# BLDC_Motor_Controller_ADP3120A.net
KiCad netlist of a schematic drawn in EAGLE
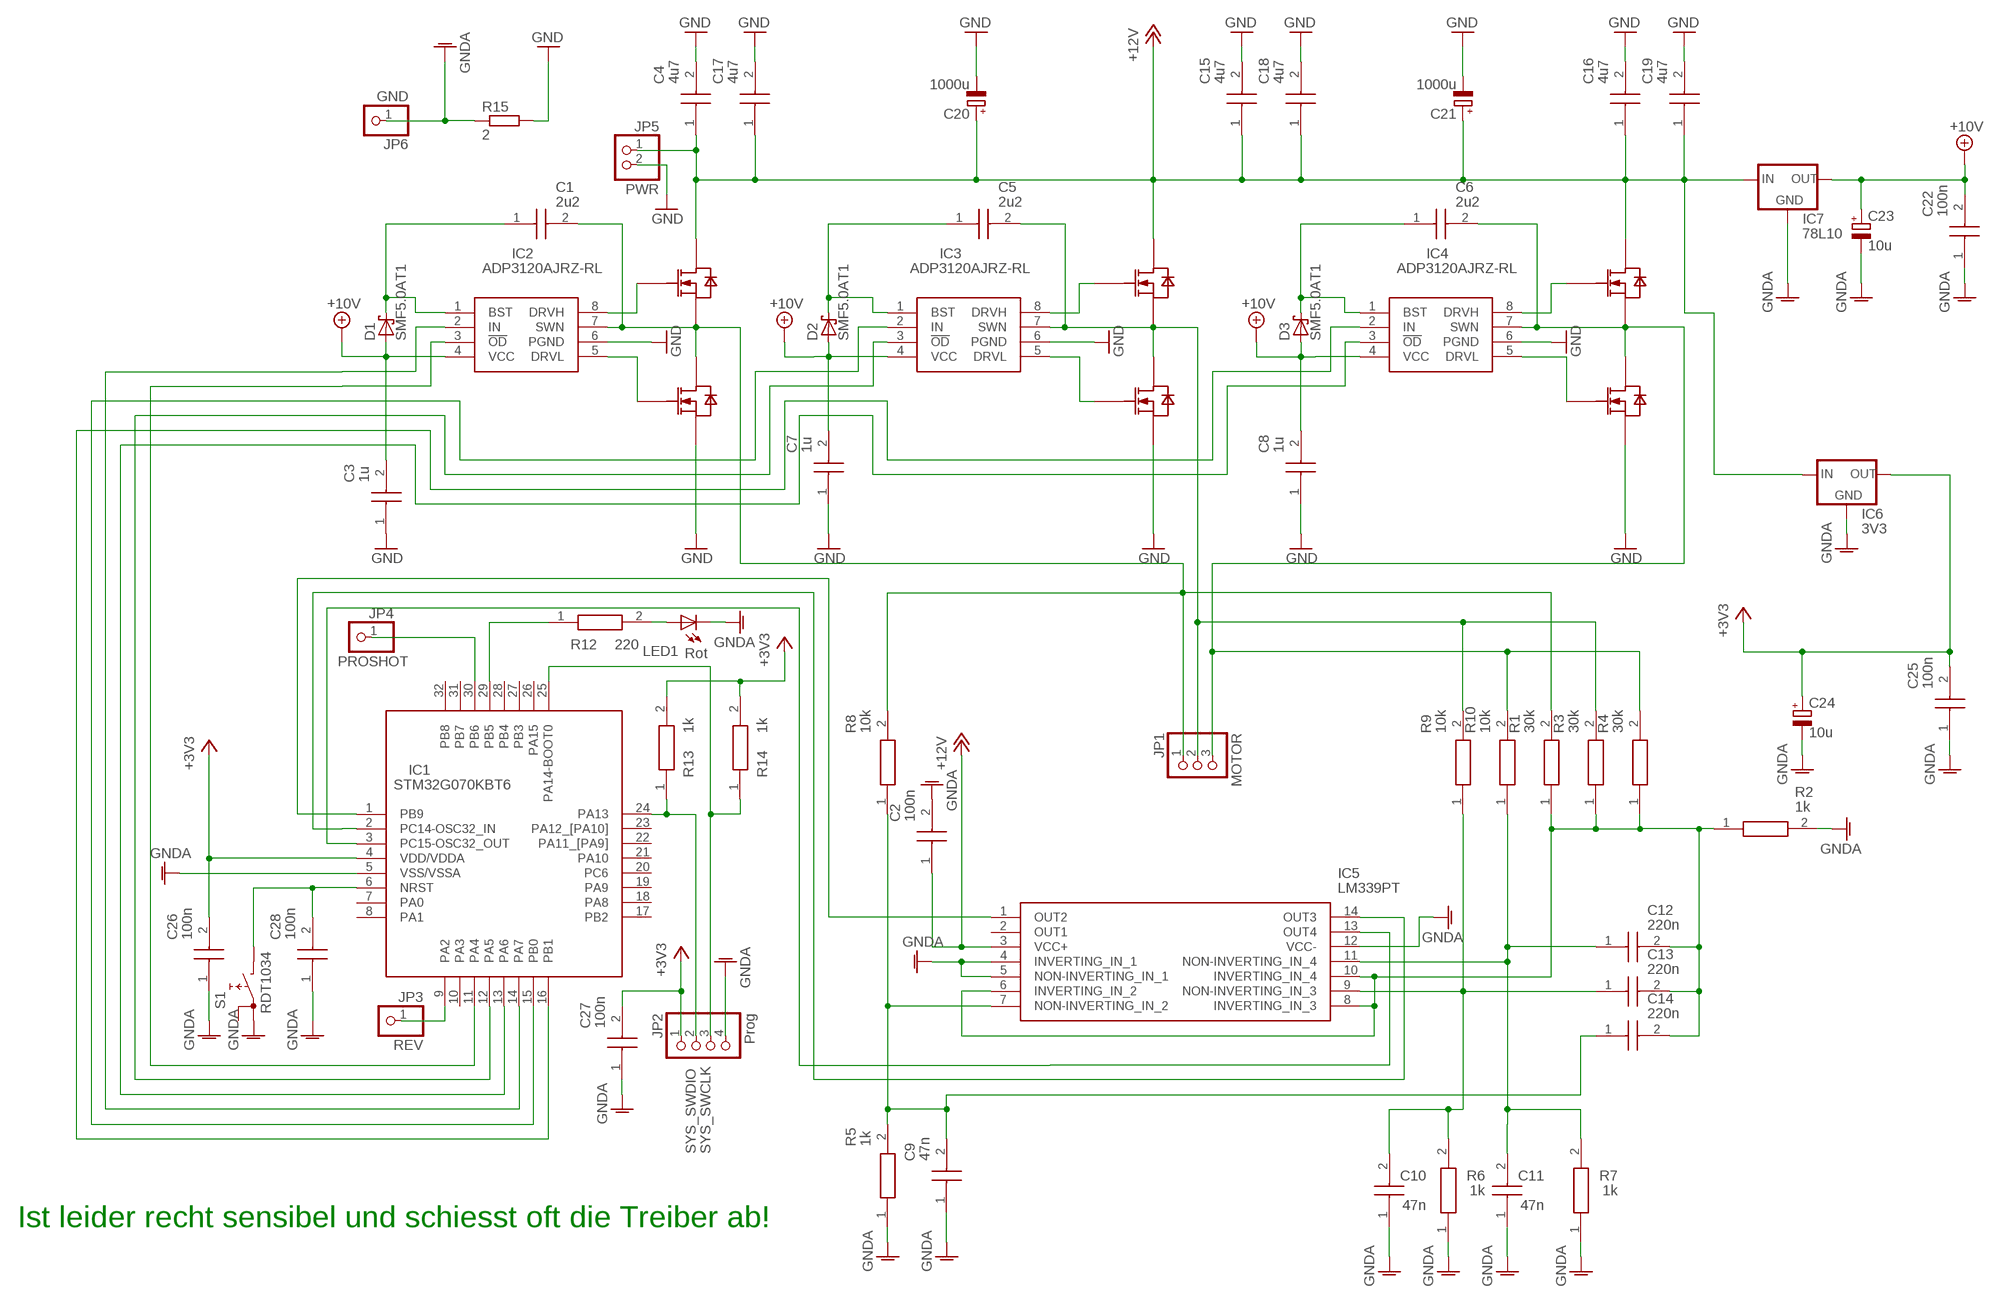
[diagram p0: schematic, sheet 1]

(export (version "E")
  (design (tool "Eeschema 10.0.6"))
  (components
    (comp (ref "C1")
      (value "2u2")
      (footprint "eagle-import:CAPC2012X135N")
      (fields
        (field (name "MANUFACTURER_PART_NUMBER") "CL21B225KAFNNNE")
        (field (name "MOUSER_PART_NUMBER") "187-CL21B225KAFNNNE")
      )
      (libsource (lib "eagle-import") (part "CL21B225KAFNNNE"))
    )
    (comp (ref "C2")
      (value "100n")
      (footprint "eagle-import:CAPC2012X145N")
      (fields
        (field (name "MANUFACTURER_PART_NUMBER") "C2012X7T2E104M125AE")
        (field (name "MOUSER_PART_NUMBER") "810-C2012X7T2E104MST")
      )
      (libsource (lib "eagle-import") (part "C2012X7T2E104M125AE"))
    )
    (comp (ref "C3")
      (value "1u")
      (footprint "eagle-import:GRM31X")
      (fields
        (field (name "MANUFACTURER_PART_NUMBER") "GRM31CC72A475KE11K")
        (field (name "MOUSER_PART_NUMBER") "81-GRM31CC72A475KE1K")
      )
      (libsource (lib "eagle-import") (part "SamacSys_Parts_GRM31CC72A475KE11K"))
    )
    (comp (ref "C4")
      (value "4u7")
      (footprint "eagle-import:GRM31X")
      (fields
        (field (name "MANUFACTURER_PART_NUMBER") "GRM31CC72A475KE11K")
        (field (name "MOUSER_PART_NUMBER") "81-GRM31CC72A475KE1K")
      )
      (libsource (lib "eagle-import") (part "GRM31CC72A475KE11K"))
    )
    (comp (ref "C5")
      (value "2u2")
      (footprint "eagle-import:CAPC2012X135N")
      (fields
        (field (name "MANUFACTURER_PART_NUMBER") "CL21B225KAFNNNE")
        (field (name "MOUSER_PART_NUMBER") "187-CL21B225KAFNNNE")
      )
      (libsource (lib "eagle-import") (part "CL21B225KAFNNNE"))
    )
    (comp (ref "C6")
      (value "2u2")
      (footprint "eagle-import:CAPC2012X135N")
      (fields
        (field (name "MANUFACTURER_PART_NUMBER") "CL21B225KAFNNNE")
        (field (name "MOUSER_PART_NUMBER") "187-CL21B225KAFNNNE")
      )
      (libsource (lib "eagle-import") (part "CL21B225KAFNNNE"))
    )
    (comp (ref "C7")
      (value "1u")
      (footprint "eagle-import:GRM31X")
      (fields
        (field (name "MANUFACTURER_PART_NUMBER") "GRM31CC72A475KE11K")
        (field (name "MOUSER_PART_NUMBER") "81-GRM31CC72A475KE1K")
      )
      (libsource (lib "eagle-import") (part "SamacSys_Parts_GRM31CC72A475KE11K"))
    )
    (comp (ref "C8")
      (value "1u")
      (footprint "eagle-import:GRM31X")
      (fields
        (field (name "MANUFACTURER_PART_NUMBER") "GRM31CC72A475KE11K")
        (field (name "MOUSER_PART_NUMBER") "81-GRM31CC72A475KE1K")
      )
      (libsource (lib "eagle-import") (part "SamacSys_Parts_GRM31CC72A475KE11K"))
    )
    (comp (ref "C9")
      (value "47n")
      (footprint "eagle-import:CAPC2012X145N")
      (fields
        (field (name "MANUFACTURER_PART_NUMBER") "C2012X7T2E104M125AE")
        (field (name "MOUSER_PART_NUMBER") "810-C2012X7T2E104MST")
      )
      (libsource (lib "eagle-import") (part "C2012X7T2E104M125AE"))
    )
    (comp (ref "C10")
      (value "47n")
      (footprint "eagle-import:CAPC2012X145N")
      (fields
        (field (name "MANUFACTURER_PART_NUMBER") "C2012X7T2E104M125AE")
        (field (name "MOUSER_PART_NUMBER") "810-C2012X7T2E104MST")
      )
      (libsource (lib "eagle-import") (part "C2012X7T2E104M125AE"))
    )
    (comp (ref "C11")
      (value "47n")
      (footprint "eagle-import:CAPC2012X145N")
      (fields
        (field (name "MANUFACTURER_PART_NUMBER") "C2012X7T2E104M125AE")
        (field (name "MOUSER_PART_NUMBER") "810-C2012X7T2E104MST")
      )
      (libsource (lib "eagle-import") (part "C2012X7T2E104M125AE"))
    )
    (comp (ref "C12")
      (value "220n")
      (footprint "eagle-import:CAPC2012X145N")
      (fields
        (field (name "MANUFACTURER_PART_NUMBER") "C2012X7T2E104M125AE")
        (field (name "MOUSER_PART_NUMBER") "810-C2012X7T2E104MST")
      )
      (libsource (lib "eagle-import") (part "C2012X7T2E104M125AE"))
    )
    (comp (ref "C13")
      (value "220n")
      (footprint "eagle-import:CAPC2012X145N")
      (fields
        (field (name "MANUFACTURER_PART_NUMBER") "C2012X7T2E104M125AE")
        (field (name "MOUSER_PART_NUMBER") "810-C2012X7T2E104MST")
      )
      (libsource (lib "eagle-import") (part "C2012X7T2E104M125AE"))
    )
    (comp (ref "C14")
      (value "220n")
      (footprint "eagle-import:CAPC2012X145N")
      (fields
        (field (name "MANUFACTURER_PART_NUMBER") "C2012X7T2E104M125AE")
        (field (name "MOUSER_PART_NUMBER") "810-C2012X7T2E104MST")
      )
      (libsource (lib "eagle-import") (part "C2012X7T2E104M125AE"))
    )
    (comp (ref "C15")
      (value "4u7")
      (footprint "eagle-import:GRM31X")
      (fields
        (field (name "MANUFACTURER_PART_NUMBER") "GRM31CC72A475KE11K")
        (field (name "MOUSER_PART_NUMBER") "81-GRM31CC72A475KE1K")
      )
      (libsource (lib "eagle-import") (part "GRM31CC72A475KE11K"))
    )
    (comp (ref "C16")
      (value "4u7")
      (footprint "eagle-import:GRM31X")
      (fields
        (field (name "MANUFACTURER_PART_NUMBER") "GRM31CC72A475KE11K")
        (field (name "MOUSER_PART_NUMBER") "81-GRM31CC72A475KE1K")
      )
      (libsource (lib "eagle-import") (part "GRM31CC72A475KE11K"))
    )
    (comp (ref "C17")
      (value "4u7")
      (footprint "eagle-import:GRM31X")
      (fields
        (field (name "MANUFACTURER_PART_NUMBER") "GRM31CC72A475KE11K")
        (field (name "MOUSER_PART_NUMBER") "81-GRM31CC72A475KE1K")
      )
      (libsource (lib "eagle-import") (part "GRM31CC72A475KE11K"))
    )
    (comp (ref "C18")
      (value "4u7")
      (footprint "eagle-import:GRM31X")
      (fields
        (field (name "MANUFACTURER_PART_NUMBER") "GRM31CC72A475KE11K")
        (field (name "MOUSER_PART_NUMBER") "81-GRM31CC72A475KE1K")
      )
      (libsource (lib "eagle-import") (part "GRM31CC72A475KE11K"))
    )
    (comp (ref "C19")
      (value "4u7")
      (footprint "eagle-import:GRM31X")
      (fields
        (field (name "MANUFACTURER_PART_NUMBER") "GRM31CC72A475KE11K")
        (field (name "MOUSER_PART_NUMBER") "81-GRM31CC72A475KE1K")
      )
      (libsource (lib "eagle-import") (part "GRM31CC72A475KE11K"))
    )
    (comp (ref "C20")
      (value "1000u")
      (footprint "eagle-import:150CLZ-0810")
      (libsource (lib "eagle-import") (part "CPOL-EU150CLZ-0810"))
    )
    (comp (ref "C21")
      (value "1000u")
      (footprint "eagle-import:150CLZ-0810")
      (libsource (lib "eagle-import") (part "CPOL-EU150CLZ-0810"))
    )
    (comp (ref "C22")
      (value "100n")
      (footprint "eagle-import:CAPC2012X145N")
      (fields
        (field (name "MANUFACTURER_PART_NUMBER") "C2012X7T2E104M125AE")
        (field (name "MOUSER_PART_NUMBER") "810-C2012X7T2E104MST")
      )
      (libsource (lib "eagle-import") (part "C2012X7T2E104M125AE"))
    )
    (comp (ref "C23")
      (value "10u")
      (footprint "eagle-import:SMC_C")
      (libsource (lib "eagle-import") (part "CPOL-EUSMCC"))
    )
    (comp (ref "C24")
      (value "10u")
      (footprint "eagle-import:SMC_C")
      (libsource (lib "eagle-import") (part "CPOL-EUSMCC"))
    )
    (comp (ref "C25")
      (value "100n")
      (footprint "eagle-import:CAPC2012X145N")
      (fields
        (field (name "MANUFACTURER_PART_NUMBER") "C2012X7T2E104M125AE")
        (field (name "MOUSER_PART_NUMBER") "810-C2012X7T2E104MST")
      )
      (libsource (lib "eagle-import") (part "C2012X7T2E104M125AE"))
    )
    (comp (ref "C26")
      (value "100n")
      (footprint "eagle-import:CAPC2012X145N")
      (fields
        (field (name "MANUFACTURER_PART_NUMBER") "C2012X7T2E104M125AE")
        (field (name "MOUSER_PART_NUMBER") "810-C2012X7T2E104MST")
      )
      (libsource (lib "eagle-import") (part "C2012X7T2E104M125AE"))
    )
    (comp (ref "C27")
      (value "100n")
      (footprint "eagle-import:CAPC2012X145N")
      (fields
        (field (name "MANUFACTURER_PART_NUMBER") "C2012X7T2E104M125AE")
        (field (name "MOUSER_PART_NUMBER") "810-C2012X7T2E104MST")
      )
      (libsource (lib "eagle-import") (part "C2012X7T2E104M125AE"))
    )
    (comp (ref "C28")
      (value "100n")
      (footprint "eagle-import:CAPC2012X145N")
      (fields
        (field (name "MANUFACTURER_PART_NUMBER") "C2012X7T2E104M125AE")
        (field (name "MOUSER_PART_NUMBER") "810-C2012X7T2E104MST")
      )
      (libsource (lib "eagle-import") (part "C2012X7T2E104M125AE"))
    )
    (comp (ref "D1")
      (value "SMF5.0AT1")
      (footprint "eagle-import:SOD123FL")
      (libsource (lib "eagle-import") (part "SMF5.0AT1"))
    )
    (comp (ref "D2")
      (value "SMF5.0AT1")
      (footprint "eagle-import:SOD123FL")
      (libsource (lib "eagle-import") (part "SMF5.0AT1"))
    )
    (comp (ref "D3")
      (value "SMF5.0AT1")
      (footprint "eagle-import:SOD123FL")
      (libsource (lib "eagle-import") (part "SMF5.0AT1"))
    )
    (comp (ref "IC1")
      (value "STM32G070KBT6")
      (footprint "eagle-import:QFP80P900X900X160-32N")
      (fields (field (name "MOUSER_PART_NUMBER") "511-STM32G070KBT6"))
      (libsource (lib "eagle-import") (part "STM32G070KBT6"))
    )
    (comp (ref "IC2")
      (value "ADP3120AJRZ-RL")
      (footprint "eagle-import:SOIC127P600X175-8N")
      (fields (field (name "MOUSER_PART_NUMBER") "863-ADP3120AJRZ-RL"))
      (libsource (lib "eagle-import") (part "ADP3120AJRZ-RL"))
    )
    (comp (ref "IC3")
      (value "ADP3120AJRZ-RL")
      (footprint "eagle-import:SOIC127P600X175-8N")
      (fields (field (name "MOUSER_PART_NUMBER") "863-ADP3120AJRZ-RL"))
      (libsource (lib "eagle-import") (part "ADP3120AJRZ-RL"))
    )
    (comp (ref "IC4")
      (value "ADP3120AJRZ-RL")
      (footprint "eagle-import:SOIC127P600X175-8N")
      (fields (field (name "MOUSER_PART_NUMBER") "863-ADP3120AJRZ-RL"))
      (libsource (lib "eagle-import") (part "ADP3120AJRZ-RL"))
    )
    (comp (ref "IC5")
      (value "LM339PT")
      (footprint "eagle-import:SOP65P640X120-14N")
      (fields (field (name "MOUSER_PART_NUMBER") "511-LM339P"))
      (libsource (lib "eagle-import") (part "LM339PT"))
    )
    (comp (ref "IC6")
      (value "3V3")
      (footprint "eagle-import:SOT89R")
      (libsource (lib "eagle-import") (part "XC63FPP"))
    )
    (comp (ref "IC7")
      (value "78L10")
      (footprint "eagle-import:SOT89R")
      (libsource (lib "eagle-import") (part "XC63FPP"))
    )
    (comp (ref "JP1")
      (value "MOTOR")
      (footprint "eagle-import:1X03")
      (libsource (lib "eagle-import") (part "PINHD-1X3"))
    )
    (comp (ref "JP2")
      (value "Prog")
      (footprint "eagle-import:1X04")
      (libsource (lib "eagle-import") (part "PINHD-1X4"))
    )
    (comp (ref "JP3")
      (value "REV")
      (footprint "eagle-import:1X01")
      (libsource (lib "eagle-import") (part "PINHD-1X1"))
    )
    (comp (ref "JP4")
      (value "PROSHOT")
      (footprint "eagle-import:1X01")
      (libsource (lib "eagle-import") (part "PINHD-1X1"))
    )
    (comp (ref "JP5")
      (value "PWR")
      (footprint "eagle-import:1X02")
      (libsource (lib "eagle-import") (part "PINHD-1X2"))
    )
    (comp (ref "JP6")
      (value "GND")
      (footprint "eagle-import:1X01")
      (libsource (lib "eagle-import") (part "PINHD-1X1"))
    )
    (comp (ref "LED1")
      (value "Rot")
      (footprint "eagle-import:SML0805")
      (libsource (lib "eagle-import") (part "LEDSML0805"))
    )
    (comp (ref "Q1")
      (value "IRFR1205TRPBF")
      (footprint "eagle-import:TO229P991X239-3_4N")
      (libsource (lib "eagle-import") (part "IRFR1205TRPBF"))
    )
    (comp (ref "Q2")
      (value "IRFR1205TRPBF")
      (footprint "eagle-import:TO229P991X239-3_4N")
      (libsource (lib "eagle-import") (part "IRFR1205TRPBF"))
    )
    (comp (ref "Q3")
      (value "IRFR1205TRPBF")
      (footprint "eagle-import:TO229P991X239-3_4N")
      (libsource (lib "eagle-import") (part "IRFR1205TRPBF"))
    )
    (comp (ref "Q4")
      (value "IRFR1205TRPBF")
      (footprint "eagle-import:TO229P991X239-3_4N")
      (libsource (lib "eagle-import") (part "IRFR1205TRPBF"))
    )
    (comp (ref "Q5")
      (value "IRFR1205TRPBF")
      (footprint "eagle-import:TO229P991X239-3_4N")
      (libsource (lib "eagle-import") (part "IRFR1205TRPBF"))
    )
    (comp (ref "Q6")
      (value "IRFR1205TRPBF")
      (footprint "eagle-import:TO229P991X239-3_4N")
      (libsource (lib "eagle-import") (part "IRFR1205TRPBF"))
    )
    (comp (ref "R1")
      (value "30k")
      (footprint "eagle-import:ERJUP6")
      (fields (field (name "MANUFACTURER_PART_NUMBER") "ERJ-UP6F1180V"))
      (libsource (lib "eagle-import") (part "ERJ-UP6F1180V"))
    )
    (comp (ref "R2")
      (value "1k")
      (footprint "eagle-import:ERJUP6")
      (fields (field (name "MANUFACTURER_PART_NUMBER") "ERJ-UP6F1180V"))
      (libsource (lib "eagle-import") (part "ERJ-UP6F1180V"))
    )
    (comp (ref "R3")
      (value "30k")
      (footprint "eagle-import:ERJUP6")
      (fields (field (name "MANUFACTURER_PART_NUMBER") "ERJ-UP6F1180V"))
      (libsource (lib "eagle-import") (part "ERJ-UP6F1180V"))
    )
    (comp (ref "R4")
      (value "30k")
      (footprint "eagle-import:ERJUP6")
      (fields (field (name "MANUFACTURER_PART_NUMBER") "ERJ-UP6F1180V"))
      (libsource (lib "eagle-import") (part "ERJ-UP6F1180V"))
    )
    (comp (ref "R5")
      (value "1k")
      (footprint "eagle-import:ERJUP6")
      (fields (field (name "MANUFACTURER_PART_NUMBER") "ERJ-UP6F1180V"))
      (libsource (lib "eagle-import") (part "ERJ-UP6F1180V"))
    )
    (comp (ref "R6")
      (value "1k")
      (footprint "eagle-import:ERJUP6")
      (fields (field (name "MANUFACTURER_PART_NUMBER") "ERJ-UP6F1180V"))
      (libsource (lib "eagle-import") (part "ERJ-UP6F1180V"))
    )
    (comp (ref "R7")
      (value "1k")
      (footprint "eagle-import:ERJUP6")
      (fields (field (name "MANUFACTURER_PART_NUMBER") "ERJ-UP6F1180V"))
      (libsource (lib "eagle-import") (part "ERJ-UP6F1180V"))
    )
    (comp (ref "R8")
      (value "10k")
      (footprint "eagle-import:ERJUP6")
      (fields (field (name "MANUFACTURER_PART_NUMBER") "ERJ-UP6F1180V"))
      (libsource (lib "eagle-import") (part "ERJ-UP6F1180V"))
    )
    (comp (ref "R9")
      (value "10k")
      (footprint "eagle-import:ERJUP6")
      (fields (field (name "MANUFACTURER_PART_NUMBER") "ERJ-UP6F1180V"))
      (libsource (lib "eagle-import") (part "ERJ-UP6F1180V"))
    )
    (comp (ref "R10")
      (value "10k")
      (footprint "eagle-import:ERJUP6")
      (fields (field (name "MANUFACTURER_PART_NUMBER") "ERJ-UP6F1180V"))
      (libsource (lib "eagle-import") (part "ERJ-UP6F1180V"))
    )
    (comp (ref "R12")
      (value "220")
      (footprint "eagle-import:ERJUP6")
      (fields (field (name "MANUFACTURER_PART_NUMBER") "ERJ-UP6F1180V"))
      (libsource (lib "eagle-import") (part "ERJ-UP6F1180V"))
    )
    (comp (ref "R13")
      (value "1k")
      (footprint "eagle-import:ERJUP6")
      (fields (field (name "MANUFACTURER_PART_NUMBER") "ERJ-UP6F1180V"))
      (libsource (lib "eagle-import") (part "ERJ-UP6F1180V"))
    )
    (comp (ref "R14")
      (value "1k")
      (footprint "eagle-import:ERJUP6")
      (fields (field (name "MANUFACTURER_PART_NUMBER") "ERJ-UP6F1180V"))
      (libsource (lib "eagle-import") (part "ERJ-UP6F1180V"))
    )
    (comp (ref "R15")
      (value "2")
      (footprint "eagle-import:R2012")
      (libsource (lib "eagle-import") (part "R-EU_R2012"))
    )
    (comp (ref "S1")
      (value "RDT1034")
      (footprint "eagle-import:RDT1034")
      (libsource (lib "eagle-import") (part "RDT1034"))
    )
  )
  (nets
    (net (code "1") (name "+3V3") (class "Default")
      (node (ref "C24") (pin "+") (pinfunction "+_+") (pintype "passive"))
      (node (ref "C25") (pin "2") (pinfunction "2_2") (pintype "bidirectional"))
      (node (ref "C26") (pin "2") (pinfunction "2_2") (pintype "bidirectional"))
      (node (ref "C27") (pin "2") (pinfunction "2_2") (pintype "bidirectional"))
      (node (ref "IC1") (pin "4") (pinfunction "VDD/VDDA_4") (pintype "power_in"))
      (node (ref "IC6") (pin "3") (pinfunction "OUT_3") (pintype "passive"))
      (node (ref "JP2") (pin "1") (pinfunction "1_1") (pintype "passive"))
      (node (ref "R13") (pin "2") (pinfunction "2_2") (pintype "bidirectional"))
      (node (ref "R14") (pin "2") (pinfunction "2_2") (pintype "bidirectional"))
    )
    (net (code "2") (name "+10V") (class "Default")
      (node (ref "C22") (pin "2") (pinfunction "2_2") (pintype "bidirectional"))
      (node (ref "C23") (pin "+") (pinfunction "+_+") (pintype "passive"))
      (node (ref "C3") (pin "2") (pinfunction "2_2") (pintype "bidirectional"))
      (node (ref "C7") (pin "2") (pinfunction "2_2") (pintype "bidirectional"))
      (node (ref "C8") (pin "2") (pinfunction "2_2") (pintype "bidirectional"))
      (node (ref "D1") (pin "A") (pinfunction "A_A") (pintype "passive"))
      (node (ref "D2") (pin "A") (pinfunction "A_A") (pintype "passive"))
      (node (ref "D3") (pin "A") (pinfunction "A_A") (pintype "passive"))
      (node (ref "IC2") (pin "4") (pinfunction "VCC_4") (pintype "power_in"))
      (node (ref "IC3") (pin "4") (pinfunction "VCC_4") (pintype "power_in"))
      (node (ref "IC4") (pin "4") (pinfunction "VCC_4") (pintype "power_in"))
      (node (ref "IC7") (pin "3") (pinfunction "OUT_3") (pintype "passive"))
    )
    (net (code "3") (name "+12V") (class "Default")
      (node (ref "C15") (pin "1") (pinfunction "1_1") (pintype "bidirectional"))
      (node (ref "C16") (pin "1") (pinfunction "1_1") (pintype "bidirectional"))
      (node (ref "C17") (pin "1") (pinfunction "1_1") (pintype "bidirectional"))
      (node (ref "C18") (pin "1") (pinfunction "1_1") (pintype "bidirectional"))
      (node (ref "C19") (pin "1") (pinfunction "1_1") (pintype "bidirectional"))
      (node (ref "C2") (pin "1") (pinfunction "1_1") (pintype "bidirectional"))
      (node (ref "C20") (pin "+") (pinfunction "+_+") (pintype "passive"))
      (node (ref "C21") (pin "+") (pinfunction "+_+") (pintype "passive"))
      (node (ref "C4") (pin "1") (pinfunction "1_1") (pintype "bidirectional"))
      (node (ref "IC5") (pin "3") (pinfunction "VCC+_3") (pintype "power_in"))
      (node (ref "IC6") (pin "2") (pinfunction "IN_2") (pintype "input"))
      (node (ref "IC7") (pin "2") (pinfunction "IN_2") (pintype "input"))
      (node (ref "JP5") (pin "1") (pinfunction "1_1") (pintype "passive"))
      (node (ref "Q1") (pin "4") (pinfunction "DRAIN_4") (pintype "passive"))
      (node (ref "Q3") (pin "4") (pinfunction "DRAIN_4") (pintype "passive"))
      (node (ref "Q5") (pin "4") (pinfunction "DRAIN_4") (pintype "passive"))
    )
    (net (code "4") (name "/SYS_SWCLK") (class "Default")
      (node (ref "IC1") (pin "25") (pinfunction "PA14-BOOT0_25") (pintype "bidirectional"))
      (node (ref "JP2") (pin "3") (pinfunction "3_3") (pintype "passive"))
      (node (ref "R14") (pin "1") (pinfunction "1_1") (pintype "bidirectional"))
    )
    (net (code "5") (name "/SYS_SWDIO") (class "Default")
      (node (ref "IC1") (pin "24") (pinfunction "PA13_24") (pintype "bidirectional"))
      (node (ref "JP2") (pin "2") (pinfunction "2_2") (pintype "passive"))
      (node (ref "R13") (pin "1") (pinfunction "1_1") (pintype "bidirectional"))
    )
    (net (code "6") (name "GND") (class "Default")
      (node (ref "C15") (pin "2") (pinfunction "2_2") (pintype "bidirectional"))
      (node (ref "C16") (pin "2") (pinfunction "2_2") (pintype "bidirectional"))
      (node (ref "C17") (pin "2") (pinfunction "2_2") (pintype "bidirectional"))
      (node (ref "C18") (pin "2") (pinfunction "2_2") (pintype "bidirectional"))
      (node (ref "C19") (pin "2") (pinfunction "2_2") (pintype "bidirectional"))
      (node (ref "C20") (pin "-") (pinfunction "-_-") (pintype "passive"))
      (node (ref "C21") (pin "-") (pinfunction "-_-") (pintype "passive"))
      (node (ref "C3") (pin "1") (pinfunction "1_1") (pintype "bidirectional"))
      (node (ref "C4") (pin "2") (pinfunction "2_2") (pintype "bidirectional"))
      (node (ref "C7") (pin "1") (pinfunction "1_1") (pintype "bidirectional"))
      (node (ref "C8") (pin "1") (pinfunction "1_1") (pintype "bidirectional"))
      (node (ref "IC2") (pin "6") (pinfunction "PGND_6") (pintype "power_in"))
      (node (ref "IC3") (pin "6") (pinfunction "PGND_6") (pintype "power_in"))
      (node (ref "IC4") (pin "6") (pinfunction "PGND_6") (pintype "power_in"))
      (node (ref "JP5") (pin "2") (pinfunction "2_2") (pintype "passive"))
      (node (ref "Q2") (pin "3") (pinfunction "SOURCE_3") (pintype "passive"))
      (node (ref "Q4") (pin "3") (pinfunction "SOURCE_3") (pintype "passive"))
      (node (ref "Q6") (pin "3") (pinfunction "SOURCE_3") (pintype "passive"))
      (node (ref "R15") (pin "2") (pinfunction "2_2") (pintype "passive"))
    )
    (net (code "7") (name "GNDA") (class "Default")
      (node (ref "C10") (pin "1") (pinfunction "1_1") (pintype "bidirectional"))
      (node (ref "C11") (pin "1") (pinfunction "1_1") (pintype "bidirectional"))
      (node (ref "C2") (pin "2") (pinfunction "2_2") (pintype "bidirectional"))
      (node (ref "C22") (pin "1") (pinfunction "1_1") (pintype "bidirectional"))
      (node (ref "C23") (pin "-") (pinfunction "-_-") (pintype "passive"))
      (node (ref "C24") (pin "-") (pinfunction "-_-") (pintype "passive"))
      (node (ref "C25") (pin "1") (pinfunction "1_1") (pintype "bidirectional"))
      (node (ref "C26") (pin "1") (pinfunction "1_1") (pintype "bidirectional"))
      (node (ref "C27") (pin "1") (pinfunction "1_1") (pintype "bidirectional"))
      (node (ref "C28") (pin "1") (pinfunction "1_1") (pintype "bidirectional"))
      (node (ref "C9") (pin "1") (pinfunction "1_1") (pintype "bidirectional"))
      (node (ref "IC1") (pin "5") (pinfunction "VSS/VSSA_5") (pintype "power_in"))
      (node (ref "IC5") (pin "12") (pinfunction "VCC-_12") (pintype "power_in"))
      (node (ref "IC5") (pin "4") (pinfunction "INVERTING_IN_1_4") (pintype "input"))
      (node (ref "IC5") (pin "5") (pinfunction "NON-INVERTING_IN_1_5") (pintype "input"))
      (node (ref "IC6") (pin "1") (pinfunction "GND_1") (pintype "input"))
      (node (ref "IC7") (pin "1") (pinfunction "GND_1") (pintype "input"))
      (node (ref "JP2") (pin "4") (pinfunction "4_4") (pintype "passive"))
      (node (ref "JP6") (pin "1") (pinfunction "1_1") (pintype "passive"))
      (node (ref "LED1") (pin "C") (pinfunction "C_C") (pintype "passive"))
      (node (ref "R15") (pin "1") (pinfunction "1_1") (pintype "passive"))
      (node (ref "R2") (pin "2") (pinfunction "2_2") (pintype "bidirectional"))
      (node (ref "R5") (pin "1") (pinfunction "1_1") (pintype "bidirectional"))
      (node (ref "R6") (pin "1") (pinfunction "1_1") (pintype "bidirectional"))
      (node (ref "R7") (pin "1") (pinfunction "1_1") (pintype "bidirectional"))
      (node (ref "S1") (pin "A1") (pinfunction "A1_A1") (pintype "passive"))
    )
    (net (code "8") (name "Net-(IC1-NRST)") (class "Default")
      (node (ref "C28") (pin "2") (pinfunction "2_2") (pintype "bidirectional"))
      (node (ref "IC1") (pin "6") (pinfunction "NRST_6") (pintype "bidirectional"))
      (node (ref "S1") (pin "B") (pinfunction "B_B") (pintype "passive"))
    )
    (net (code "9") (name "Net-(IC1-PA2)") (class "Default")
      (node (ref "IC1") (pin "9") (pinfunction "PA2_9") (pintype "bidirectional"))
      (node (ref "JP3") (pin "1") (pinfunction "1_1") (pintype "passive"))
    )
    (net (code "10") (name "Net-(IC1-PA4)") (class "Default")
      (node (ref "IC1") (pin "11") (pinfunction "PA4_11") (pintype "bidirectional"))
      (node (ref "IC2") (pin "3") (pinfunction "~{OD}_3") (pintype "bidirectional"))
    )
    (net (code "11") (name "Net-(IC1-PA5)") (class "Default")
      (node (ref "IC1") (pin "12") (pinfunction "PA5_12") (pintype "bidirectional"))
      (node (ref "IC3") (pin "3") (pinfunction "~{OD}_3") (pintype "bidirectional"))
    )
    (net (code "12") (name "Net-(IC1-PA6)") (class "Default")
      (node (ref "IC1") (pin "13") (pinfunction "PA6_13") (pintype "bidirectional"))
      (node (ref "IC4") (pin "3") (pinfunction "~{OD}_3") (pintype "bidirectional"))
    )
    (net (code "13") (name "Net-(IC1-PA7)") (class "Default")
      (node (ref "IC1") (pin "14") (pinfunction "PA7_14") (pintype "bidirectional"))
      (node (ref "IC2") (pin "2") (pinfunction "IN_2") (pintype "input"))
    )
    (net (code "14") (name "Net-(IC1-PB0)") (class "Default")
      (node (ref "IC1") (pin "15") (pinfunction "PB0_15") (pintype "bidirectional"))
      (node (ref "IC3") (pin "2") (pinfunction "IN_2") (pintype "input"))
    )
    (net (code "15") (name "Net-(IC1-PB1)") (class "Default")
      (node (ref "IC1") (pin "16") (pinfunction "PB1_16") (pintype "bidirectional"))
      (node (ref "IC4") (pin "2") (pinfunction "IN_2") (pintype "input"))
    )
    (net (code "16") (name "Net-(IC1-PB5)") (class "Default")
      (node (ref "IC1") (pin "29") (pinfunction "PB5_29") (pintype "bidirectional"))
      (node (ref "R12") (pin "1") (pinfunction "1_1") (pintype "bidirectional"))
    )
    (net (code "17") (name "Net-(IC1-PB6)") (class "Default")
      (node (ref "IC1") (pin "30") (pinfunction "PB6_30") (pintype "bidirectional"))
      (node (ref "JP4") (pin "1") (pinfunction "1_1") (pintype "passive"))
    )
    (net (code "18") (name "Net-(IC1-PB9)") (class "Default")
      (node (ref "IC1") (pin "1") (pinfunction "PB9_1") (pintype "bidirectional"))
      (node (ref "IC5") (pin "1") (pinfunction "OUT2_1") (pintype "output"))
    )
    (net (code "19") (name "Net-(IC1-PC14-OSC32_IN)") (class "Default")
      (node (ref "IC1") (pin "2") (pinfunction "PC14-OSC32_IN_2") (pintype "bidirectional"))
      (node (ref "IC5") (pin "14") (pinfunction "OUT3_14") (pintype "output"))
    )
    (net (code "20") (name "Net-(IC1-PC15-OSC32_OUT)") (class "Default")
      (node (ref "IC1") (pin "3") (pinfunction "PC15-OSC32_OUT_3") (pintype "bidirectional"))
      (node (ref "IC5") (pin "13") (pinfunction "OUT4_13") (pintype "output"))
    )
    (net (code "21") (name "Net-(IC2-BST)") (class "Default")
      (node (ref "C1") (pin "1") (pinfunction "1_1") (pintype "bidirectional"))
      (node (ref "D1") (pin "C") (pinfunction "C_C") (pintype "passive"))
      (node (ref "IC2") (pin "1") (pinfunction "BST_1") (pintype "bidirectional"))
    )
    (net (code "22") (name "Net-(IC2-DRVH)") (class "Default")
      (node (ref "IC2") (pin "8") (pinfunction "DRVH_8") (pintype "bidirectional"))
      (node (ref "Q1") (pin "1") (pinfunction "GATE_1") (pintype "passive"))
    )
    (net (code "23") (name "Net-(IC2-DRVL)") (class "Default")
      (node (ref "IC2") (pin "5") (pinfunction "DRVL_5") (pintype "bidirectional"))
      (node (ref "Q2") (pin "1") (pinfunction "GATE_1") (pintype "passive"))
    )
    (net (code "24") (name "Net-(IC2-SWN)") (class "Default")
      (node (ref "C1") (pin "2") (pinfunction "2_2") (pintype "bidirectional"))
      (node (ref "IC2") (pin "7") (pinfunction "SWN_7") (pintype "bidirectional"))
      (node (ref "JP1") (pin "1") (pinfunction "1_1") (pintype "passive"))
      (node (ref "Q1") (pin "3") (pinfunction "SOURCE_3") (pintype "passive"))
      (node (ref "Q2") (pin "4") (pinfunction "DRAIN_4") (pintype "passive"))
      (node (ref "R1") (pin "2") (pinfunction "2_2") (pintype "bidirectional"))
      (node (ref "R8") (pin "2") (pinfunction "2_2") (pintype "bidirectional"))
    )
    (net (code "25") (name "Net-(IC3-BST)") (class "Default")
      (node (ref "C5") (pin "1") (pinfunction "1_1") (pintype "bidirectional"))
      (node (ref "D2") (pin "C") (pinfunction "C_C") (pintype "passive"))
      (node (ref "IC3") (pin "1") (pinfunction "BST_1") (pintype "bidirectional"))
    )
    (net (code "26") (name "Net-(IC3-DRVH)") (class "Default")
      (node (ref "IC3") (pin "8") (pinfunction "DRVH_8") (pintype "bidirectional"))
      (node (ref "Q3") (pin "1") (pinfunction "GATE_1") (pintype "passive"))
    )
    (net (code "27") (name "Net-(IC3-DRVL)") (class "Default")
      (node (ref "IC3") (pin "5") (pinfunction "DRVL_5") (pintype "bidirectional"))
      (node (ref "Q4") (pin "1") (pinfunction "GATE_1") (pintype "passive"))
    )
    (net (code "28") (name "Net-(IC3-SWN)") (class "Default")
      (node (ref "C5") (pin "2") (pinfunction "2_2") (pintype "bidirectional"))
      (node (ref "IC3") (pin "7") (pinfunction "SWN_7") (pintype "bidirectional"))
      (node (ref "JP1") (pin "2") (pinfunction "2_2") (pintype "passive"))
      (node (ref "Q3") (pin "3") (pinfunction "SOURCE_3") (pintype "passive"))
      (node (ref "Q4") (pin "4") (pinfunction "DRAIN_4") (pintype "passive"))
      (node (ref "R3") (pin "2") (pinfunction "2_2") (pintype "bidirectional"))
      (node (ref "R9") (pin "2") (pinfunction "2_2") (pintype "bidirectional"))
    )
    (net (code "29") (name "Net-(IC4-BST)") (class "Default")
      (node (ref "C6") (pin "1") (pinfunction "1_1") (pintype "bidirectional"))
      (node (ref "D3") (pin "C") (pinfunction "C_C") (pintype "passive"))
      (node (ref "IC4") (pin "1") (pinfunction "BST_1") (pintype "bidirectional"))
    )
    (net (code "30") (name "Net-(IC4-DRVH)") (class "Default")
      (node (ref "IC4") (pin "8") (pinfunction "DRVH_8") (pintype "bidirectional"))
      (node (ref "Q5") (pin "1") (pinfunction "GATE_1") (pintype "passive"))
    )
    (net (code "31") (name "Net-(IC4-DRVL)") (class "Default")
      (node (ref "IC4") (pin "5") (pinfunction "DRVL_5") (pintype "bidirectional"))
      (node (ref "Q6") (pin "1") (pinfunction "GATE_1") (pintype "passive"))
    )
    (net (code "32") (name "Net-(IC4-SWN)") (class "Default")
      (node (ref "C6") (pin "2") (pinfunction "2_2") (pintype "bidirectional"))
      (node (ref "IC4") (pin "7") (pinfunction "SWN_7") (pintype "bidirectional"))
      (node (ref "JP1") (pin "3") (pinfunction "3_3") (pintype "passive"))
      (node (ref "Q5") (pin "3") (pinfunction "SOURCE_3") (pintype "passive"))
      (node (ref "Q6") (pin "4") (pinfunction "DRAIN_4") (pintype "passive"))
      (node (ref "R10") (pin "2") (pinfunction "2_2") (pintype "bidirectional"))
      (node (ref "R4") (pin "2") (pinfunction "2_2") (pintype "bidirectional"))
    )
    (net (code "33") (name "Net-(IC5-INVERTING_IN_2)") (class "Default")
      (node (ref "C12") (pin "2") (pinfunction "2_2") (pintype "bidirectional"))
      (node (ref "C13") (pin "2") (pinfunction "2_2") (pintype "bidirectional"))
      (node (ref "C14") (pin "2") (pinfunction "2_2") (pintype "bidirectional"))
      (node (ref "IC5") (pin "10") (pinfunction "INVERTING_IN_4_10") (pintype "input"))
      (node (ref "IC5") (pin "6") (pinfunction "INVERTING_IN_2_6") (pintype "input"))
      (node (ref "IC5") (pin "8") (pinfunction "INVERTING_IN_3_8") (pintype "input"))
      (node (ref "R1") (pin "1") (pinfunction "1_1") (pintype "bidirectional"))
      (node (ref "R2") (pin "1") (pinfunction "1_1") (pintype "bidirectional"))
      (node (ref "R3") (pin "1") (pinfunction "1_1") (pintype "bidirectional"))
      (node (ref "R4") (pin "1") (pinfunction "1_1") (pintype "bidirectional"))
    )
    (net (code "34") (name "Net-(IC5-NON-INVERTING_IN_2)") (class "Default")
      (node (ref "C14") (pin "1") (pinfunction "1_1") (pintype "bidirectional"))
      (node (ref "C9") (pin "2") (pinfunction "2_2") (pintype "bidirectional"))
      (node (ref "IC5") (pin "7") (pinfunction "NON-INVERTING_IN_2_7") (pintype "input"))
      (node (ref "R5") (pin "2") (pinfunction "2_2") (pintype "bidirectional"))
      (node (ref "R8") (pin "1") (pinfunction "1_1") (pintype "bidirectional"))
    )
    (net (code "35") (name "Net-(IC5-NON-INVERTING_IN_3)") (class "Default")
      (node (ref "C10") (pin "2") (pinfunction "2_2") (pintype "bidirectional"))
      (node (ref "C13") (pin "1") (pinfunction "1_1") (pintype "bidirectional"))
      (node (ref "IC5") (pin "9") (pinfunction "NON-INVERTING_IN_3_9") (pintype "input"))
      (node (ref "R6") (pin "2") (pinfunction "2_2") (pintype "bidirectional"))
      (node (ref "R9") (pin "1") (pinfunction "1_1") (pintype "bidirectional"))
    )
    (net (code "36") (name "Net-(IC5-NON-INVERTING_IN_4)") (class "Default")
      (node (ref "C11") (pin "2") (pinfunction "2_2") (pintype "bidirectional"))
      (node (ref "C12") (pin "1") (pinfunction "1_1") (pintype "bidirectional"))
      (node (ref "IC5") (pin "11") (pinfunction "NON-INVERTING_IN_4_11") (pintype "input"))
      (node (ref "R10") (pin "1") (pinfunction "1_1") (pintype "bidirectional"))
      (node (ref "R7") (pin "2") (pinfunction "2_2") (pintype "bidirectional"))
    )
    (net (code "37") (name "Net-(LED1-PadA)") (class "Default")
      (node (ref "LED1") (pin "A") (pinfunction "A_A") (pintype "passive"))
      (node (ref "R12") (pin "2") (pinfunction "2_2") (pintype "bidirectional"))
    )
    (net (code "38") (name "unconnected-(IC1-PA0-Pad7)") (class "Default")
      (node (ref "IC1") (pin "7") (pinfunction "PA0_7") (pintype "bidirectional"))
    )
    (net (code "39") (name "unconnected-(IC1-PA1-Pad8)") (class "Default")
      (node (ref "IC1") (pin "8") (pinfunction "PA1_8") (pintype "bidirectional"))
    )
    (net (code "40") (name "unconnected-(IC1-PA3-Pad10)") (class "Default")
      (node (ref "IC1") (pin "10") (pinfunction "PA3_10") (pintype "bidirectional"))
    )
    (net (code "41") (name "unconnected-(IC1-PA8-Pad18)") (class "Default")
      (node (ref "IC1") (pin "18") (pinfunction "PA8_18") (pintype "bidirectional"))
    )
    (net (code "42") (name "unconnected-(IC1-PA9-Pad19)") (class "Default")
      (node (ref "IC1") (pin "19") (pinfunction "PA9_19") (pintype "bidirectional"))
    )
    (net (code "43") (name "unconnected-(IC1-PA10-Pad21)") (class "Default")
      (node (ref "IC1") (pin "21") (pinfunction "PA10_21") (pintype "bidirectional"))
    )
    (net (code "44") (name "unconnected-(IC1-PA11_[PA9]-Pad22)") (class "Default")
      (node (ref "IC1") (pin "22") (pinfunction "PA11_[PA9]_22") (pintype "bidirectional"))
    )
    (net (code "45") (name "unconnected-(IC1-PA12_[PA10]-Pad23)") (class "Default")
      (node (ref "IC1") (pin "23") (pinfunction "PA12_[PA10]_23") (pintype "bidirectional"))
    )
    (net (code "46") (name "unconnected-(IC1-PA15-Pad26)") (class "Default")
      (node (ref "IC1") (pin "26") (pinfunction "PA15_26") (pintype "bidirectional"))
    )
    (net (code "47") (name "unconnected-(IC1-PB2-Pad17)") (class "Default")
      (node (ref "IC1") (pin "17") (pinfunction "PB2_17") (pintype "bidirectional"))
    )
    (net (code "48") (name "unconnected-(IC1-PB3-Pad27)") (class "Default")
      (node (ref "IC1") (pin "27") (pinfunction "PB3_27") (pintype "bidirectional"))
    )
    (net (code "49") (name "unconnected-(IC1-PB4-Pad28)") (class "Default")
      (node (ref "IC1") (pin "28") (pinfunction "PB4_28") (pintype "bidirectional"))
    )
    (net (code "50") (name "unconnected-(IC1-PB7-Pad31)") (class "Default")
      (node (ref "IC1") (pin "31") (pinfunction "PB7_31") (pintype "bidirectional"))
    )
    (net (code "51") (name "unconnected-(IC1-PB8-Pad32)") (class "Default")
      (node (ref "IC1") (pin "32") (pinfunction "PB8_32") (pintype "bidirectional"))
    )
    (net (code "52") (name "unconnected-(IC1-PC6-Pad20)") (class "Default")
      (node (ref "IC1") (pin "20") (pinfunction "PC6_20") (pintype "bidirectional"))
    )
    (net (code "53") (name "unconnected-(IC5-OUT1-Pad2)") (class "Default")
      (node (ref "IC5") (pin "2") (pinfunction "OUT1_2") (pintype "output"))
    )
    (net (code "54") (name "unconnected-(S1-PadA)") (class "Default")
      (node (ref "S1") (pin "A") (pinfunction "A_A") (pintype "passive"))
    )
  )
)
